# JESD204B.net
KiCad netlist of a schematic drawn in Altium Designer
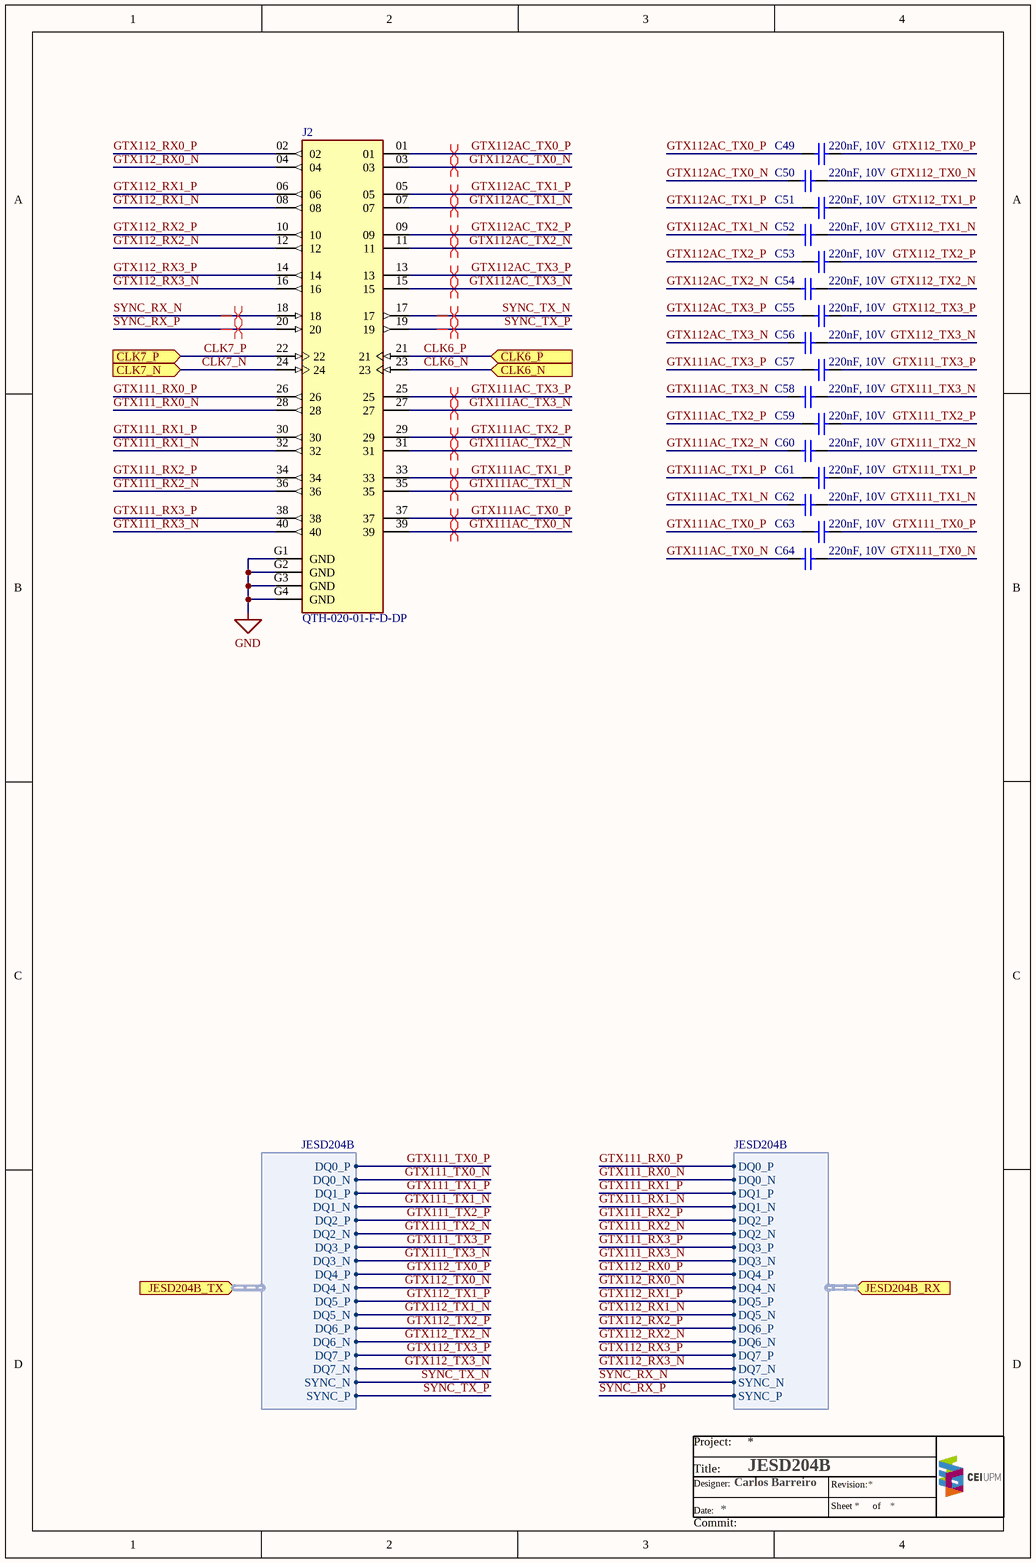
[diagram p0: JESD204B.SchDoc]

(export (version "E")
  (design (tool "Eeschema 10.0.6"))
  (components
    (comp (ref "C49")
      (value "220nF, 10V")
      (footprint "WURTH_WCAP-CSGP_0402")
      (description "WCAP-CSGP Multilayer Ceramic Chip Capacitor, General Purpose, size 0402, X5R, 220nF, 10V")
      (fields
        (field (name "MANUFACTURER PART NUMBER") "885012105011")
        (field (name "MANUFACTURER") "Wurth Elektronik")
      )
      (libsource (lib "SpaceVNXBaseBoard") (part "885012105011"))
    )
    (comp (ref "C50")
      (value "220nF, 10V")
      (footprint "WURTH_WCAP-CSGP_0402")
      (description "WCAP-CSGP Multilayer Ceramic Chip Capacitor, General Purpose, size 0402, X5R, 220nF, 10V")
      (fields
        (field (name "MANUFACTURER PART NUMBER") "885012105011")
        (field (name "MANUFACTURER") "Wurth Elektronik")
      )
      (libsource (lib "SpaceVNXBaseBoard") (part "885012105011"))
    )
    (comp (ref "C51")
      (value "220nF, 10V")
      (footprint "WURTH_WCAP-CSGP_0402")
      (description "WCAP-CSGP Multilayer Ceramic Chip Capacitor, General Purpose, size 0402, X5R, 220nF, 10V")
      (fields
        (field (name "MANUFACTURER PART NUMBER") "885012105011")
        (field (name "MANUFACTURER") "Wurth Elektronik")
      )
      (libsource (lib "SpaceVNXBaseBoard") (part "885012105011"))
    )
    (comp (ref "C52")
      (value "220nF, 10V")
      (footprint "WURTH_WCAP-CSGP_0402")
      (description "WCAP-CSGP Multilayer Ceramic Chip Capacitor, General Purpose, size 0402, X5R, 220nF, 10V")
      (fields
        (field (name "MANUFACTURER PART NUMBER") "885012105011")
        (field (name "MANUFACTURER") "Wurth Elektronik")
      )
      (libsource (lib "SpaceVNXBaseBoard") (part "885012105011"))
    )
    (comp (ref "C53")
      (value "220nF, 10V")
      (footprint "WURTH_WCAP-CSGP_0402")
      (description "WCAP-CSGP Multilayer Ceramic Chip Capacitor, General Purpose, size 0402, X5R, 220nF, 10V")
      (fields
        (field (name "MANUFACTURER PART NUMBER") "885012105011")
        (field (name "MANUFACTURER") "Wurth Elektronik")
      )
      (libsource (lib "SpaceVNXBaseBoard") (part "885012105011"))
    )
    (comp (ref "C54")
      (value "220nF, 10V")
      (footprint "WURTH_WCAP-CSGP_0402")
      (description "WCAP-CSGP Multilayer Ceramic Chip Capacitor, General Purpose, size 0402, X5R, 220nF, 10V")
      (fields
        (field (name "MANUFACTURER PART NUMBER") "885012105011")
        (field (name "MANUFACTURER") "Wurth Elektronik")
      )
      (libsource (lib "SpaceVNXBaseBoard") (part "885012105011"))
    )
    (comp (ref "C55")
      (value "220nF, 10V")
      (footprint "WURTH_WCAP-CSGP_0402")
      (description "WCAP-CSGP Multilayer Ceramic Chip Capacitor, General Purpose, size 0402, X5R, 220nF, 10V")
      (fields
        (field (name "MANUFACTURER PART NUMBER") "885012105011")
        (field (name "MANUFACTURER") "Wurth Elektronik")
      )
      (libsource (lib "SpaceVNXBaseBoard") (part "885012105011"))
    )
    (comp (ref "C56")
      (value "220nF, 10V")
      (footprint "WURTH_WCAP-CSGP_0402")
      (description "WCAP-CSGP Multilayer Ceramic Chip Capacitor, General Purpose, size 0402, X5R, 220nF, 10V")
      (fields
        (field (name "MANUFACTURER PART NUMBER") "885012105011")
        (field (name "MANUFACTURER") "Wurth Elektronik")
      )
      (libsource (lib "SpaceVNXBaseBoard") (part "885012105011"))
    )
    (comp (ref "C57")
      (value "220nF, 10V")
      (footprint "WURTH_WCAP-CSGP_0402")
      (description "WCAP-CSGP Multilayer Ceramic Chip Capacitor, General Purpose, size 0402, X5R, 220nF, 10V")
      (fields
        (field (name "MANUFACTURER PART NUMBER") "885012105011")
        (field (name "MANUFACTURER") "Wurth Elektronik")
      )
      (libsource (lib "SpaceVNXBaseBoard") (part "885012105011"))
    )
    (comp (ref "C58")
      (value "220nF, 10V")
      (footprint "WURTH_WCAP-CSGP_0402")
      (description "WCAP-CSGP Multilayer Ceramic Chip Capacitor, General Purpose, size 0402, X5R, 220nF, 10V")
      (fields
        (field (name "MANUFACTURER PART NUMBER") "885012105011")
        (field (name "MANUFACTURER") "Wurth Elektronik")
      )
      (libsource (lib "SpaceVNXBaseBoard") (part "885012105011"))
    )
    (comp (ref "C59")
      (value "220nF, 10V")
      (footprint "WURTH_WCAP-CSGP_0402")
      (description "WCAP-CSGP Multilayer Ceramic Chip Capacitor, General Purpose, size 0402, X5R, 220nF, 10V")
      (fields
        (field (name "MANUFACTURER PART NUMBER") "885012105011")
        (field (name "MANUFACTURER") "Wurth Elektronik")
      )
      (libsource (lib "SpaceVNXBaseBoard") (part "885012105011"))
    )
    (comp (ref "C60")
      (value "220nF, 10V")
      (footprint "WURTH_WCAP-CSGP_0402")
      (description "WCAP-CSGP Multilayer Ceramic Chip Capacitor, General Purpose, size 0402, X5R, 220nF, 10V")
      (fields
        (field (name "MANUFACTURER PART NUMBER") "885012105011")
        (field (name "MANUFACTURER") "Wurth Elektronik")
      )
      (libsource (lib "SpaceVNXBaseBoard") (part "885012105011"))
    )
    (comp (ref "C61")
      (value "220nF, 10V")
      (footprint "WURTH_WCAP-CSGP_0402")
      (description "WCAP-CSGP Multilayer Ceramic Chip Capacitor, General Purpose, size 0402, X5R, 220nF, 10V")
      (fields
        (field (name "MANUFACTURER PART NUMBER") "885012105011")
        (field (name "MANUFACTURER") "Wurth Elektronik")
      )
      (libsource (lib "SpaceVNXBaseBoard") (part "885012105011"))
    )
    (comp (ref "C62")
      (value "220nF, 10V")
      (footprint "WURTH_WCAP-CSGP_0402")
      (description "WCAP-CSGP Multilayer Ceramic Chip Capacitor, General Purpose, size 0402, X5R, 220nF, 10V")
      (fields
        (field (name "MANUFACTURER PART NUMBER") "885012105011")
        (field (name "MANUFACTURER") "Wurth Elektronik")
      )
      (libsource (lib "SpaceVNXBaseBoard") (part "885012105011"))
    )
    (comp (ref "C63")
      (value "220nF, 10V")
      (footprint "WURTH_WCAP-CSGP_0402")
      (description "WCAP-CSGP Multilayer Ceramic Chip Capacitor, General Purpose, size 0402, X5R, 220nF, 10V")
      (fields
        (field (name "MANUFACTURER PART NUMBER") "885012105011")
        (field (name "MANUFACTURER") "Wurth Elektronik")
      )
      (libsource (lib "SpaceVNXBaseBoard") (part "885012105011"))
    )
    (comp (ref "C64")
      (value "220nF, 10V")
      (footprint "WURTH_WCAP-CSGP_0402")
      (description "WCAP-CSGP Multilayer Ceramic Chip Capacitor, General Purpose, size 0402, X5R, 220nF, 10V")
      (fields
        (field (name "MANUFACTURER PART NUMBER") "885012105011")
        (field (name "MANUFACTURER") "Wurth Elektronik")
      )
      (libsource (lib "SpaceVNXBaseBoard") (part "885012105011"))
    )
    (comp (ref "J2")
      (value "QTH-020-01-F-D-DP")
      (footprint "SAMTEC_QTH-020-01-X-D-DP-A")
      (description "0.50 mm Q Pairs® High-Speed Ground Plane Terminal Strip, Differential Pair")
      (fields (field (name "MF") "Samtec"))
      (libsource (lib "SpaceVNXBaseBoard") (part "QTH-020-01-F-D-DP"))
    )
  )
  (nets
    (net (code "2") (name "/CLK6_N") (class "Default")
      (node (ref "J2") (pin "23") (pinfunction "23_23") (pintype "input"))
    )
    (net (code "3") (name "/CLK6_P") (class "Default")
      (node (ref "J2") (pin "21") (pinfunction "21_21") (pintype "input"))
    )
    (net (code "4") (name "/CLK7_N") (class "Default")
      (node (ref "J2") (pin "24") (pinfunction "24_24") (pintype "input"))
    )
    (net (code "5") (name "/CLK7_P") (class "Default")
      (node (ref "J2") (pin "22") (pinfunction "22_22") (pintype "input"))
    )
    (net (code "6") (name "/GTX111AC_TX0_N") (class "Default")
      (node (ref "C64") (pin "1") (pinfunction "1_1") (pintype "passive"))
      (node (ref "J2") (pin "39") (pinfunction "39_39") (pintype "passive"))
    )
    (net (code "7") (name "/GTX111AC_TX0_P") (class "Default")
      (node (ref "C63") (pin "1") (pinfunction "1_1") (pintype "passive"))
      (node (ref "J2") (pin "37") (pinfunction "37_37") (pintype "passive"))
    )
    (net (code "8") (name "/GTX111AC_TX1_N") (class "Default")
      (node (ref "C62") (pin "1") (pinfunction "1_1") (pintype "passive"))
      (node (ref "J2") (pin "35") (pinfunction "35_35") (pintype "passive"))
    )
    (net (code "9") (name "/GTX111AC_TX1_P") (class "Default")
      (node (ref "C61") (pin "1") (pinfunction "1_1") (pintype "passive"))
      (node (ref "J2") (pin "33") (pinfunction "33_33") (pintype "passive"))
    )
    (net (code "10") (name "/GTX111AC_TX2_N") (class "Default")
      (node (ref "C60") (pin "1") (pinfunction "1_1") (pintype "passive"))
      (node (ref "J2") (pin "31") (pinfunction "31_31") (pintype "passive"))
    )
    (net (code "11") (name "/GTX111AC_TX2_P") (class "Default")
      (node (ref "C59") (pin "1") (pinfunction "1_1") (pintype "passive"))
      (node (ref "J2") (pin "29") (pinfunction "29_29") (pintype "passive"))
    )
    (net (code "12") (name "/GTX111AC_TX3_N") (class "Default")
      (node (ref "C58") (pin "1") (pinfunction "1_1") (pintype "passive"))
      (node (ref "J2") (pin "27") (pinfunction "27_27") (pintype "passive"))
    )
    (net (code "13") (name "/GTX111AC_TX3_P") (class "Default")
      (node (ref "C57") (pin "1") (pinfunction "1_1") (pintype "passive"))
      (node (ref "J2") (pin "25") (pinfunction "25_25") (pintype "passive"))
    )
    (net (code "14") (name "/GTX111_RX0_N") (class "Default")
      (node (ref "J2") (pin "28") (pinfunction "28_28") (pintype "output"))
    )
    (net (code "15") (name "/GTX111_RX0_P") (class "Default")
      (node (ref "J2") (pin "26") (pinfunction "26_26") (pintype "output"))
    )
    (net (code "16") (name "/GTX111_RX1_N") (class "Default")
      (node (ref "J2") (pin "32") (pinfunction "32_32") (pintype "output"))
    )
    (net (code "17") (name "/GTX111_RX1_P") (class "Default")
      (node (ref "J2") (pin "30") (pinfunction "30_30") (pintype "output"))
    )
    (net (code "18") (name "/GTX111_RX2_N") (class "Default")
      (node (ref "J2") (pin "36") (pinfunction "36_36") (pintype "output"))
    )
    (net (code "19") (name "/GTX111_RX2_P") (class "Default")
      (node (ref "J2") (pin "34") (pinfunction "34_34") (pintype "output"))
    )
    (net (code "20") (name "/GTX111_RX3_N") (class "Default")
      (node (ref "J2") (pin "40") (pinfunction "40_40") (pintype "output"))
    )
    (net (code "21") (name "/GTX111_RX3_P") (class "Default")
      (node (ref "J2") (pin "38") (pinfunction "38_38") (pintype "output"))
    )
    (net (code "22") (name "/GTX111_TX0_N") (class "Default")
      (node (ref "C64") (pin "2") (pinfunction "2_2") (pintype "passive"))
    )
    (net (code "23") (name "/GTX111_TX0_P") (class "Default")
      (node (ref "C63") (pin "2") (pinfunction "2_2") (pintype "passive"))
    )
    (net (code "24") (name "/GTX111_TX1_N") (class "Default")
      (node (ref "C62") (pin "2") (pinfunction "2_2") (pintype "passive"))
    )
    (net (code "25") (name "/GTX111_TX1_P") (class "Default")
      (node (ref "C61") (pin "2") (pinfunction "2_2") (pintype "passive"))
    )
    (net (code "26") (name "/GTX111_TX2_N") (class "Default")
      (node (ref "C60") (pin "2") (pinfunction "2_2") (pintype "passive"))
    )
    (net (code "27") (name "/GTX111_TX2_P") (class "Default")
      (node (ref "C59") (pin "2") (pinfunction "2_2") (pintype "passive"))
    )
    (net (code "28") (name "/GTX111_TX3_N") (class "Default")
      (node (ref "C58") (pin "2") (pinfunction "2_2") (pintype "passive"))
    )
    (net (code "29") (name "/GTX111_TX3_P") (class "Default")
      (node (ref "C57") (pin "2") (pinfunction "2_2") (pintype "passive"))
    )
    (net (code "30") (name "/GTX112AC_TX0_N") (class "Default")
      (node (ref "C50") (pin "1") (pinfunction "1_1") (pintype "passive"))
      (node (ref "J2") (pin "03") (pinfunction "03_03") (pintype "passive"))
    )
    (net (code "31") (name "/GTX112AC_TX0_P") (class "Default")
      (node (ref "C49") (pin "1") (pinfunction "1_1") (pintype "passive"))
      (node (ref "J2") (pin "01") (pinfunction "01_01") (pintype "passive"))
    )
    (net (code "32") (name "/GTX112AC_TX1_N") (class "Default")
      (node (ref "C52") (pin "1") (pinfunction "1_1") (pintype "passive"))
      (node (ref "J2") (pin "07") (pinfunction "07_07") (pintype "passive"))
    )
    (net (code "33") (name "/GTX112AC_TX1_P") (class "Default")
      (node (ref "C51") (pin "1") (pinfunction "1_1") (pintype "passive"))
      (node (ref "J2") (pin "05") (pinfunction "05_05") (pintype "passive"))
    )
    (net (code "34") (name "/GTX112AC_TX2_N") (class "Default")
      (node (ref "C54") (pin "1") (pinfunction "1_1") (pintype "passive"))
      (node (ref "J2") (pin "11") (pinfunction "11_11") (pintype "passive"))
    )
    (net (code "35") (name "/GTX112AC_TX2_P") (class "Default")
      (node (ref "C53") (pin "1") (pinfunction "1_1") (pintype "passive"))
      (node (ref "J2") (pin "09") (pinfunction "09_09") (pintype "passive"))
    )
    (net (code "36") (name "/GTX112AC_TX3_N") (class "Default")
      (node (ref "C56") (pin "1") (pinfunction "1_1") (pintype "passive"))
      (node (ref "J2") (pin "15") (pinfunction "15_15") (pintype "passive"))
    )
    (net (code "37") (name "/GTX112AC_TX3_P") (class "Default")
      (node (ref "C55") (pin "1") (pinfunction "1_1") (pintype "passive"))
      (node (ref "J2") (pin "13") (pinfunction "13_13") (pintype "passive"))
    )
    (net (code "38") (name "/GTX112_RX0_N") (class "Default")
      (node (ref "J2") (pin "04") (pinfunction "04_04") (pintype "output"))
    )
    (net (code "39") (name "/GTX112_RX0_P") (class "Default")
      (node (ref "J2") (pin "02") (pinfunction "02_02") (pintype "output"))
    )
    (net (code "40") (name "/GTX112_RX1_N") (class "Default")
      (node (ref "J2") (pin "08") (pinfunction "08_08") (pintype "output"))
    )
    (net (code "41") (name "/GTX112_RX1_P") (class "Default")
      (node (ref "J2") (pin "06") (pinfunction "06_06") (pintype "output"))
    )
    (net (code "42") (name "/GTX112_RX2_N") (class "Default")
      (node (ref "J2") (pin "12") (pinfunction "12_12") (pintype "output"))
    )
    (net (code "43") (name "/GTX112_RX2_P") (class "Default")
      (node (ref "J2") (pin "10") (pinfunction "10_10") (pintype "output"))
    )
    (net (code "44") (name "/GTX112_RX3_N") (class "Default")
      (node (ref "J2") (pin "16") (pinfunction "16_16") (pintype "output"))
    )
    (net (code "45") (name "/GTX112_RX3_P") (class "Default")
      (node (ref "J2") (pin "14") (pinfunction "14_14") (pintype "output"))
    )
    (net (code "46") (name "/GTX112_TX0_N") (class "Default")
      (node (ref "C50") (pin "2") (pinfunction "2_2") (pintype "passive"))
    )
    (net (code "47") (name "/GTX112_TX0_P") (class "Default")
      (node (ref "C49") (pin "2") (pinfunction "2_2") (pintype "passive"))
    )
    (net (code "48") (name "/GTX112_TX1_N") (class "Default")
      (node (ref "C52") (pin "2") (pinfunction "2_2") (pintype "passive"))
    )
    (net (code "49") (name "/GTX112_TX1_P") (class "Default")
      (node (ref "C51") (pin "2") (pinfunction "2_2") (pintype "passive"))
    )
    (net (code "50") (name "/GTX112_TX2_N") (class "Default")
      (node (ref "C54") (pin "2") (pinfunction "2_2") (pintype "passive"))
    )
    (net (code "51") (name "/GTX112_TX2_P") (class "Default")
      (node (ref "C53") (pin "2") (pinfunction "2_2") (pintype "passive"))
    )
    (net (code "52") (name "/GTX112_TX3_N") (class "Default")
      (node (ref "C56") (pin "2") (pinfunction "2_2") (pintype "passive"))
    )
    (net (code "53") (name "/GTX112_TX3_P") (class "Default")
      (node (ref "C55") (pin "2") (pinfunction "2_2") (pintype "passive"))
    )
    (net (code "54") (name "/SYNC_RX_N") (class "Default")
      (node (ref "J2") (pin "18") (pinfunction "18_18") (pintype "input"))
    )
    (net (code "55") (name "/SYNC_RX_P") (class "Default")
      (node (ref "J2") (pin "20") (pinfunction "20_20") (pintype "input"))
    )
    (net (code "56") (name "/SYNC_TX_N") (class "Default")
      (node (ref "J2") (pin "17") (pinfunction "17_17") (pintype "output"))
    )
    (net (code "57") (name "/SYNC_TX_P") (class "Default")
      (node (ref "J2") (pin "19") (pinfunction "19_19") (pintype "output"))
    )
    (net (code "59") (name "GND") (class "Default")
      (node (ref "J2") (pin "G1") (pinfunction "GND_G1") (pintype "power_in"))
      (node (ref "J2") (pin "G2") (pinfunction "GND_G2") (pintype "power_in"))
      (node (ref "J2") (pin "G3") (pinfunction "GND_G3") (pintype "power_in"))
      (node (ref "J2") (pin "G4") (pinfunction "GND_G4") (pintype "power_in"))
    )
  )
)
